# msp430_pogo.net
KiCad netlist of a schematic drawn in EAGLE
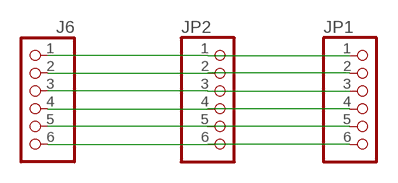
[diagram p0: schematic, sheet 1]

(export (version "E")
  (design (tool "Eeschema 10.0.6"))
  (components
    (comp (ref "J6")
      (value "PH1X650MIL")
      (footprint "eagle-import:PH1X6_50MIL")
      (libsource (lib "eagle-import") (part "PH1X650MIL"))
    )
    (comp (ref "JP1")
      (value "PINHD-1X6")
      (footprint "eagle-import:1X06")
      (libsource (lib "eagle-import") (part "PINHD-1X6"))
    )
    (comp (ref "JP2")
      (value "PINHD-1X6")
      (footprint "eagle-import:1X06")
      (libsource (lib "eagle-import") (part "PINHD-1X6"))
    )
  )
  (nets
    (net (code "1") (name "Net-(J6-Pad1)") (class "Default")
      (node (ref "J6") (pin "1") (pinfunction "1_1") (pintype "passive"))
      (node (ref "JP1") (pin "1") (pinfunction "1_1") (pintype "passive"))
      (node (ref "JP2") (pin "1") (pinfunction "1_1") (pintype "passive"))
    )
    (net (code "2") (name "Net-(J6-Pad2)") (class "Default")
      (node (ref "J6") (pin "2") (pinfunction "2_2") (pintype "passive"))
      (node (ref "JP1") (pin "2") (pinfunction "2_2") (pintype "passive"))
      (node (ref "JP2") (pin "2") (pinfunction "2_2") (pintype "passive"))
    )
    (net (code "3") (name "Net-(J6-Pad3)") (class "Default")
      (node (ref "J6") (pin "3") (pinfunction "3_3") (pintype "passive"))
      (node (ref "JP1") (pin "3") (pinfunction "3_3") (pintype "passive"))
      (node (ref "JP2") (pin "3") (pinfunction "3_3") (pintype "passive"))
    )
    (net (code "4") (name "Net-(J6-Pad4)") (class "Default")
      (node (ref "J6") (pin "4") (pinfunction "4_4") (pintype "passive"))
      (node (ref "JP1") (pin "4") (pinfunction "4_4") (pintype "passive"))
      (node (ref "JP2") (pin "4") (pinfunction "4_4") (pintype "passive"))
    )
    (net (code "5") (name "Net-(J6-Pad5)") (class "Default")
      (node (ref "J6") (pin "5") (pinfunction "5_5") (pintype "passive"))
      (node (ref "JP1") (pin "5") (pinfunction "5_5") (pintype "passive"))
      (node (ref "JP2") (pin "5") (pinfunction "5_5") (pintype "passive"))
    )
    (net (code "6") (name "Net-(J6-Pad6)") (class "Default")
      (node (ref "J6") (pin "6") (pinfunction "6_6") (pintype "passive"))
      (node (ref "JP1") (pin "6") (pinfunction "6_6") (pintype "passive"))
      (node (ref "JP2") (pin "6") (pinfunction "6_6") (pintype "passive"))
    )
  )
)
